# Power_VCC1V8.net
KiCad netlist of a schematic drawn in Altium Designer
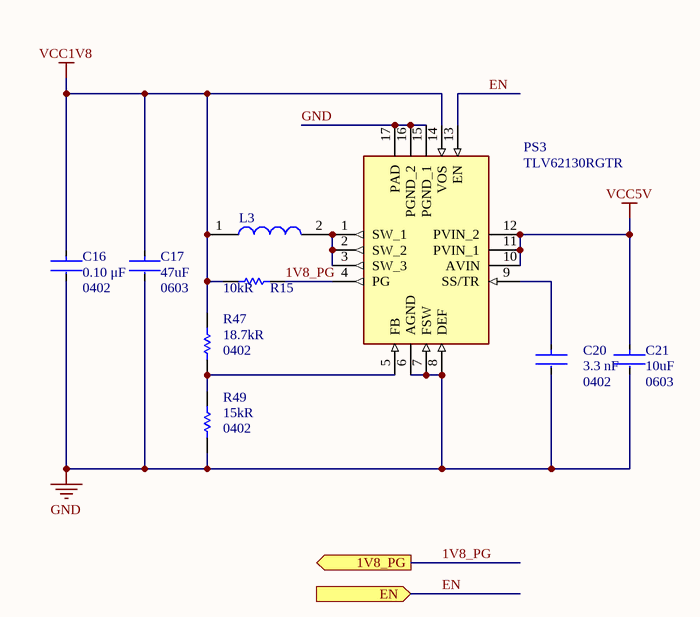
[diagram p0: Power_VCC1V8.SchDoc]

(export (version "E")
  (design (tool "Eeschema 10.0.6"))
  (components
    (comp (ref "C16")
      (value "0.10 μF")
      (footprint "FP-C0402-BB-MFG")
      (description "CAP CER 0.1UF 10V X5R 0402")
      (fields
        (field (name "MANUFACTURER") "Kemet")
        (field (name "TOLERANCE") "0.1")
        (field (name "CASE/PACKAGE") "0402")
      )
      (libsource (lib "Altium Content Vault") (part "b4654b650e69147ec39a6b967a45e02"))
    )
    (comp (ref "C17")
      (value "47uF")
      (footprint "FP-GRM188-0_2-IPC_B")
      (description "Chip Multilayer Ceramic Capacitors for General Purpose, 0603, 47uF, X5R, 15%, 20%, 6.3V")
      (fields
        (field (name "CASE CODE (IMPERIAL)") "0603")
        (field (name "TOLERANCE") "20%")
        (field (name "MANUFACTURER") "Murata")
      )
      (libsource (lib "Altium Content Vault") (part "11868f565c42a9108669ba33697ecf6"))
    )
    (comp (ref "C20")
      (value "3.3 nF")
      (footprint "FP-CC0402-MFG")
      (description "CAP CER 3300PF 50V X7R 0402")
      (fields
        (field (name "OCTOPART") "https://octopart.com/cc0402krx7r9bb332-yageo-192887")
        (field (name "MANUFACTURER") "YAGEO")
        (field (name "CASE/PACKAGE") "0402")
      )
      (libsource (lib "Altium Content Vault") (part "11868f565c42a9108669ba33697ecf6"))
    )
    (comp (ref "C21")
      (value "10uF")
      (footprint "FP-GRM188-0_1-e0_2_0_55-IPC_A")
      (description "Chip Multilayer Ceramic Capacitors for General Purpose, 0603, 10uF, X5R, 15%, 20%, 6.3V")
      (fields
        (field (name "CASE/PACKAGE") "0603")
        (field (name "VOLTAGE") "6.3V")
        (field (name "TOLERANCE") "20%")
      )
      (libsource (lib "Altium Content Vault") (part "02cd4be3c70576c341d710602a673aa"))
    )
    (comp (ref "L3")
      (value "252012CDMCDS2R2MC")
      (footprint "INDPM2520X120N")
      (description "Inductor")
      (fields (field (name "MANUFACTURER_PART_NUMBER") "252012CDMCDS‐2R2MC"))
      (libsource (lib "CCZynq") (part "252012CDMCDS2R2MC"))
    )
    (comp (ref "PS3")
      (value "TLV62130RGTR")
      (footprint "FP-RGT0016C-MFG")
      (description "Buck Switching Regulator IC Positive Adjustable 0.9V 1 Output 3A 16-VFQFN Exposed Pad")
      (fields
        (field (name "MOUSER PART NUMBER") "595-TLV62130RGTR")
        (field (name "MANUFACTURER") "Texas Instruments")
      )
      (libsource (lib "HamedLib") (part "TLV62130RGTR"))
    )
    (comp (ref "R15")
      (value "10kR")
      (footprint "RESC1005X40X25LL05T10")
      (description "10K 0402 1% 1/16W +-100PPM")
      (fields (field (name "PART NUMBER") "RC0402FR-0710KL") (field (name "MANUFACTURER") "Yageo / Phycomp"))
      (libsource (lib "Altium Content Vault") (part "RES"))
    )
    (comp (ref "R47")
      (value "18.7kR")
      (footprint "RESC1005X40X25ML05T05")
      (fields
        (field (name "PART NUMBER") "ERJ-2RKF1872X")
        (field (name "MANUFACTURER") "Panasonic")
        (field (name "CASE/PACKAGE") "0402")
        (field (name "TOLERANCE") "1%")
      )
      (libsource (lib "Altium Content Vault") (part "RES"))
    )
    (comp (ref "R49")
      (value "15kR")
      (footprint "RESC1005X40X25NL10T10")
      (fields
        (field (name "PART NUMBER") "ERA2AEB153X")
        (field (name "MANUFACTURER") "Panasonic")
        (field (name "MANUFACTURER PART NUMBER") "ERA-2AEB153X")
        (field (name "CASE/PACKAGE") "0402")
      )
      (libsource (lib "Altium Content Vault") (part "RES"))
    )
  )
  (nets
    (net (code "1") (name "/1V8_PG") (class "Default")
      (node (ref "PS3") (pin "4") (pinfunction "PG_4") (pintype "output"))
      (node (ref "R15") (pin "2") (pinfunction "2_2") (pintype "passive"))
    )
    (net (code "2") (name "/EN") (class "Default")
      (node (ref "PS3") (pin "13") (pinfunction "EN_13") (pintype "input"))
    )
    (net (code "3") (name "GND") (class "Default")
      (node (ref "C16") (pin "2") (pinfunction "2_2") (pintype "passive"))
      (node (ref "C17") (pin "2") (pinfunction "2_2") (pintype "passive"))
      (node (ref "C20") (pin "2") (pinfunction "2_2") (pintype "passive"))
      (node (ref "C21") (pin "2") (pinfunction "2_2") (pintype "passive"))
      (node (ref "PS3") (pin "15") (pinfunction "PGND_1_15") (pintype "power_in"))
      (node (ref "PS3") (pin "16") (pinfunction "PGND_2_16") (pintype "power_in"))
      (node (ref "PS3") (pin "17") (pinfunction "PAD_17") (pintype "power_in"))
      (node (ref "PS3") (pin "6") (pinfunction "AGND_6") (pintype "power_in"))
      (node (ref "PS3") (pin "7") (pinfunction "FSW_7") (pintype "input"))
      (node (ref "PS3") (pin "8") (pinfunction "DEF_8") (pintype "input"))
      (node (ref "R49") (pin "1") (pinfunction "1_1") (pintype "passive"))
    )
    (net (code "4") (name "Net-(PS3-FB)") (class "Default")
      (node (ref "PS3") (pin "5") (pinfunction "FB_5") (pintype "input"))
      (node (ref "R47") (pin "1") (pinfunction "1_1") (pintype "passive"))
      (node (ref "R49") (pin "2") (pinfunction "2_2") (pintype "passive"))
    )
    (net (code "5") (name "Net-(PS3-SS{slash}TR)") (class "Default")
      (node (ref "C20") (pin "1") (pinfunction "1_1") (pintype "passive"))
      (node (ref "PS3") (pin "9") (pinfunction "SS/TR_9") (pintype "input"))
    )
    (net (code "6") (name "Net-(PS3-SW_1)") (class "Default")
      (node (ref "L3") (pin "2") (pinfunction "2_2") (pintype "passive"))
      (node (ref "PS3") (pin "1") (pinfunction "SW_1_1") (pintype "output"))
      (node (ref "PS3") (pin "2") (pinfunction "SW_2_2") (pintype "output"))
      (node (ref "PS3") (pin "3") (pinfunction "SW_3_3") (pintype "output"))
    )
    (net (code "7") (name "VCC1V8") (class "Default")
      (node (ref "C16") (pin "1") (pinfunction "1_1") (pintype "passive"))
      (node (ref "C17") (pin "1") (pinfunction "1_1") (pintype "passive"))
      (node (ref "L3") (pin "1") (pinfunction "1_1") (pintype "passive"))
      (node (ref "PS3") (pin "14") (pinfunction "VOS_14") (pintype "input"))
      (node (ref "R15") (pin "1") (pinfunction "1_1") (pintype "passive"))
      (node (ref "R47") (pin "2") (pinfunction "2_2") (pintype "passive"))
    )
    (net (code "8") (name "VCC5V") (class "Default")
      (node (ref "C21") (pin "1") (pinfunction "1_1") (pintype "passive"))
      (node (ref "PS3") (pin "10") (pinfunction "AVIN_10") (pintype "power_in"))
      (node (ref "PS3") (pin "11") (pinfunction "PVIN_1_11") (pintype "power_in"))
      (node (ref "PS3") (pin "12") (pinfunction "PVIN_2_12") (pintype "power_in"))
    )
  )
)
